# SCH_OnBoard_2023-10-19.net
KiCad netlist of a schematic drawn in EasyEDA
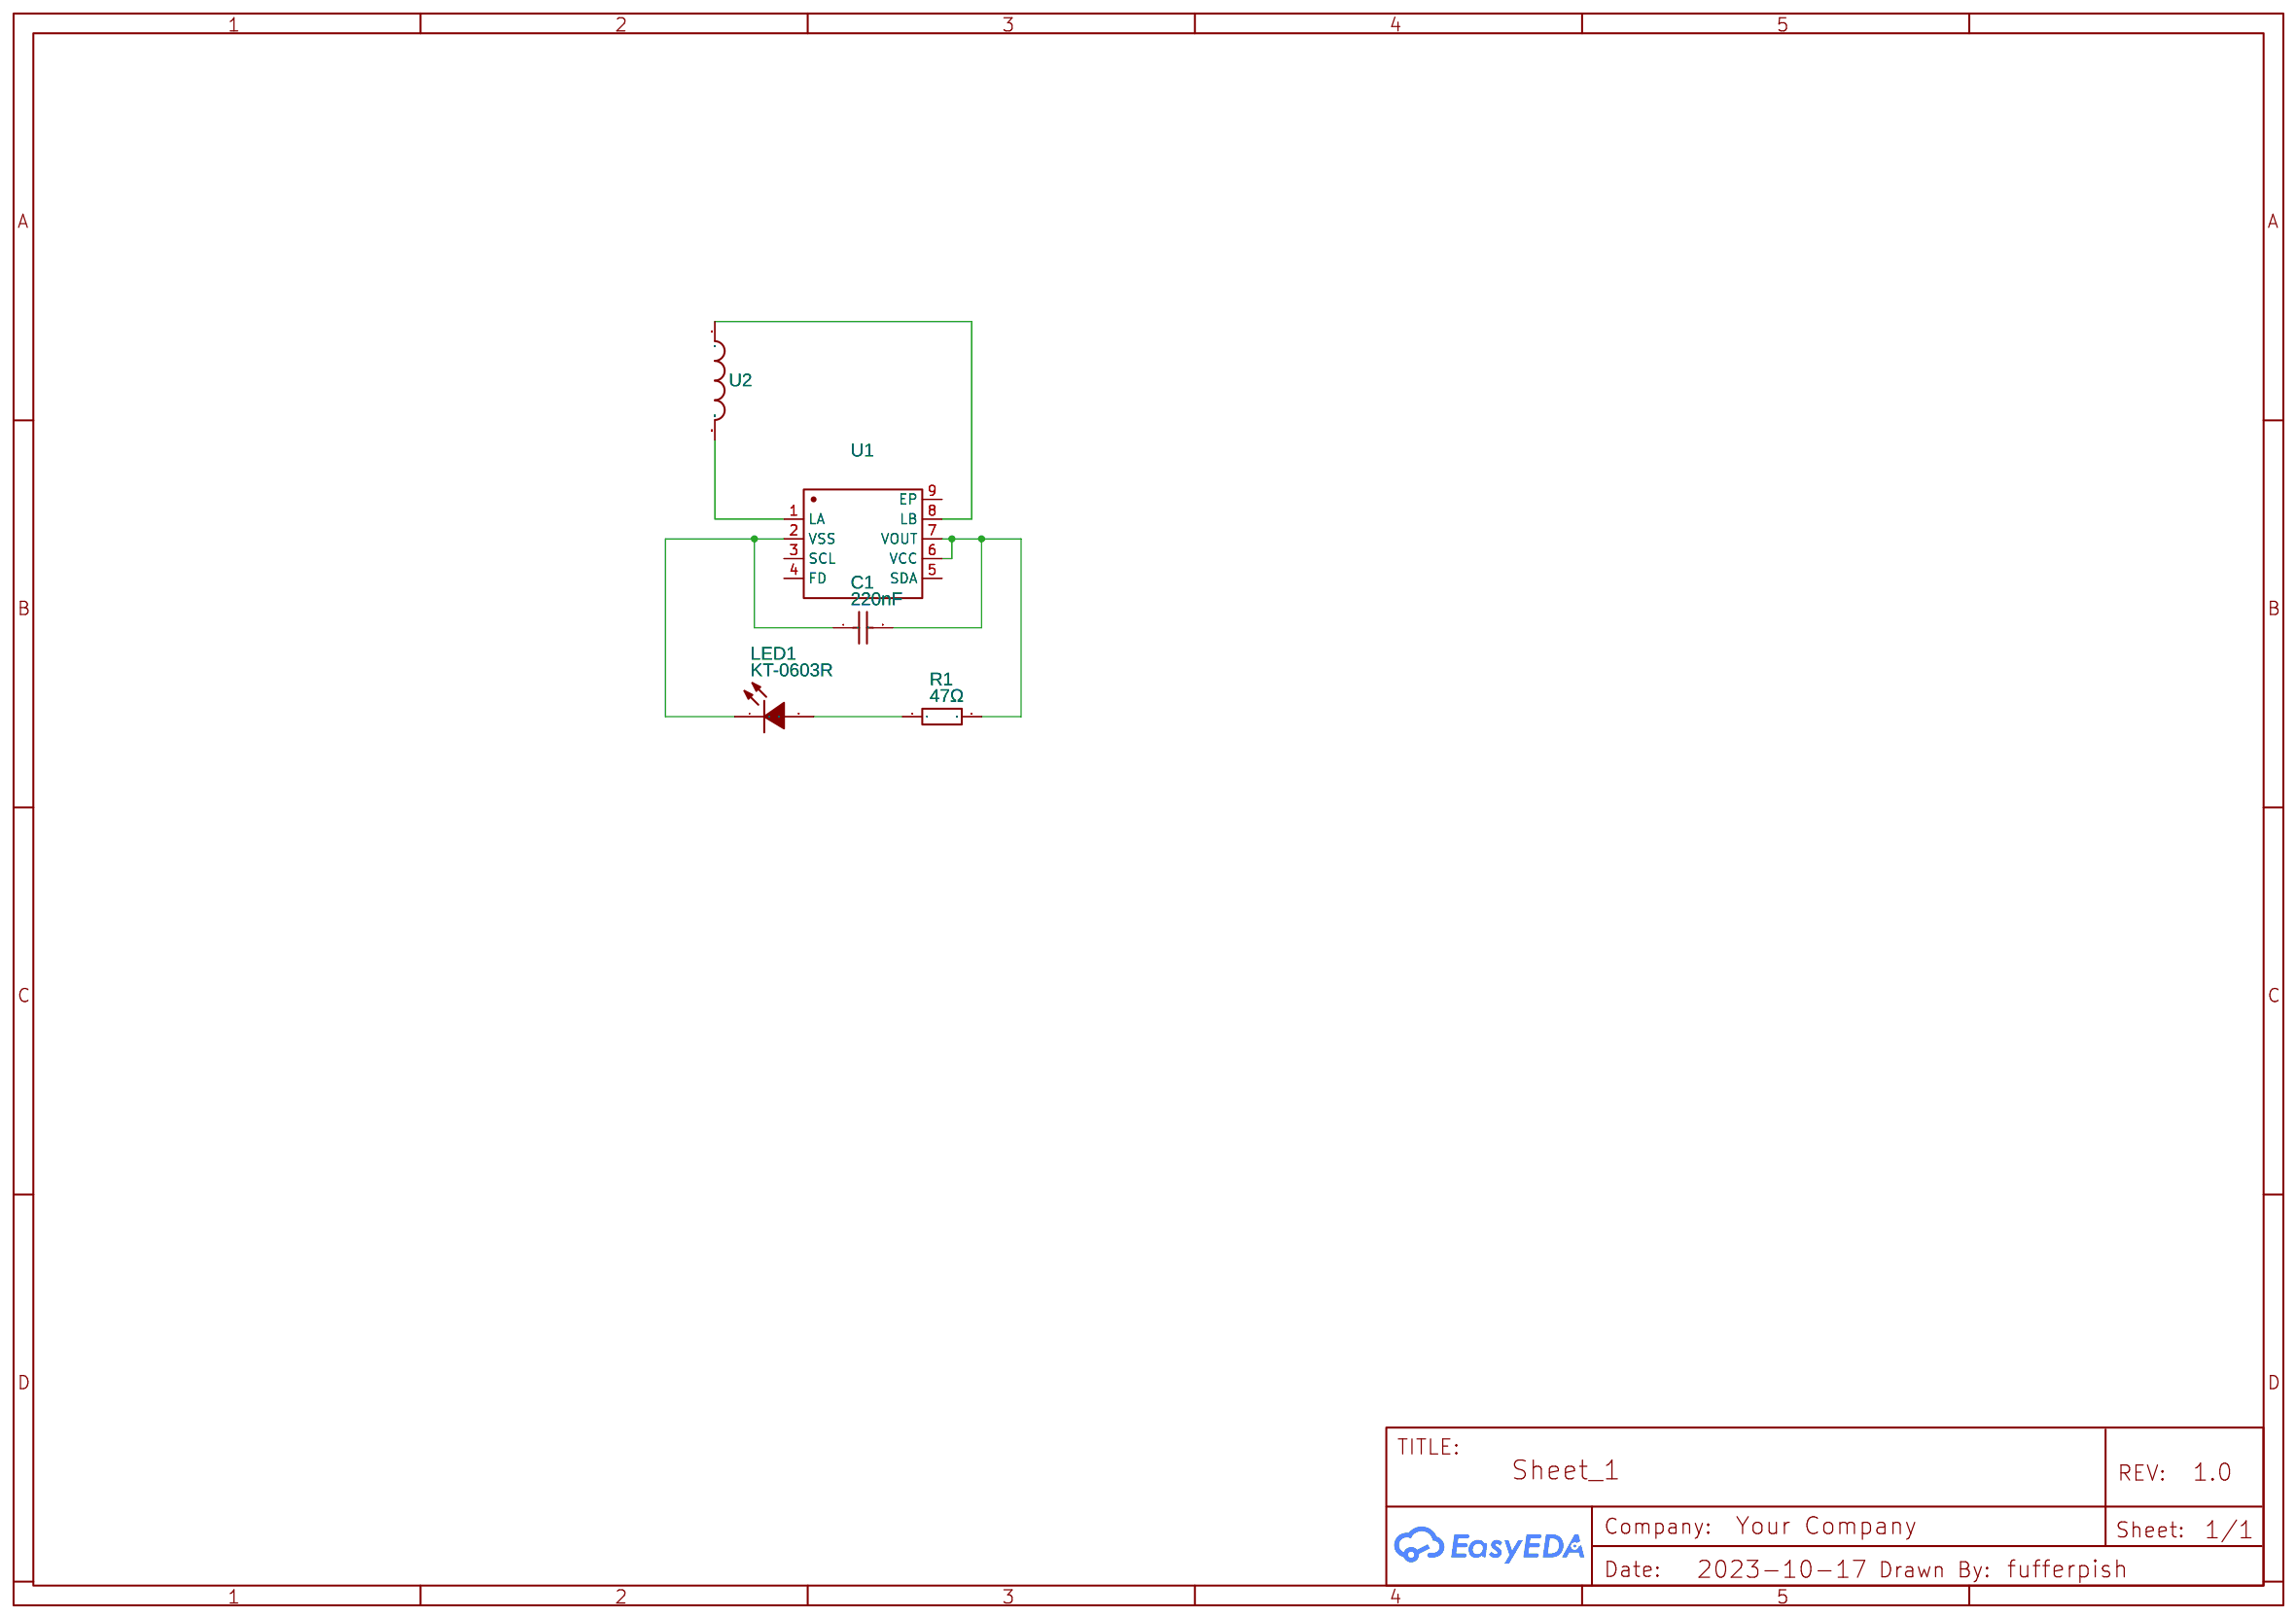
[diagram p0: schematic sheet]

(export (version "E")
  (design (tool "Eeschema 10.0.6"))
  (components
    (comp (ref "C1")
      (value "220nF")
      (fields
        (field (name "Manufacturer Part") "CL10B224KA8NNNC")
        (field (name "Manufacturer") "SAMSUNG(三星)")
      )
      (libsource (lib "") (part "CL10B224KA8NNNC"))
    )
    (comp (ref "LED1")
      (value "KT-0603R")
      (fields (field (name "Manufacturer") "KENTO"))
      (libsource (lib "") (part "KT-0603R"))
    )
    (comp (ref "R1")
      (value "47Ω")
      (fields
        (field (name "Manufacturer Part") "0603WAF470JT5E")
        (field (name "Manufacturer") "UNI-ROYAL(厚声)")
      )
      (libsource (lib "") (part "0603WAF470JT5E"))
    )
    (comp (ref "U1")
      (value "NT3H2111W0FHKH")
      (fields (field (name "Manufacturer") "NXP(恩智浦)"))
      (libsource (lib "") (part "NT3H2111W0FHKH"))
    )
    (comp (ref "U2") (value "NO") (libsource (lib "") (part "25X48MM_NFC_ANTENNA")))
  )
  (nets
    (net (code "1") (name "Net-(LED1-A)") (class "Default")
      (node (ref "LED1") (pin "2") (pinfunction "A_2") (pintype "unspecified"))
      (node (ref "R1") (pin "1") (pinfunction "1_1") (pintype "input"))
    )
    (net (code "2") (name "Net-(LED1-K)") (class "Default")
      (node (ref "C1") (pin "1") (pinfunction "1_1") (pintype "input"))
      (node (ref "LED1") (pin "1") (pinfunction "K_1") (pintype "unspecified"))
      (node (ref "U1") (pin "2") (pinfunction "VSS_2") (pintype "unspecified"))
    )
    (net (code "3") (name "Net-(U1-LA)") (class "Default")
      (node (ref "U1") (pin "1") (pinfunction "LA_1") (pintype "unspecified"))
      (node (ref "U2") (pin "P$2") (pinfunction "P$2_P$2") (pintype "bidirectional"))
    )
    (net (code "4") (name "Net-(U1-LB)") (class "Default")
      (node (ref "U1") (pin "8") (pinfunction "LB_8") (pintype "unspecified"))
      (node (ref "U2") (pin "P$1") (pinfunction "P$1_P$1") (pintype "bidirectional"))
    )
    (net (code "5") (name "Net-(U1-VCC)") (class "Default")
      (node (ref "C1") (pin "2") (pinfunction "2_2") (pintype "input"))
      (node (ref "R1") (pin "2") (pinfunction "2_2") (pintype "input"))
      (node (ref "U1") (pin "6") (pinfunction "VCC_6") (pintype "unspecified"))
      (node (ref "U1") (pin "7") (pinfunction "VOUT_7") (pintype "unspecified"))
    )
    (net (code "6") (name "unconnected-(U1-EP-Pad9)") (class "Default")
      (node (ref "U1") (pin "9") (pinfunction "EP_9") (pintype "unspecified"))
    )
    (net (code "7") (name "unconnected-(U1-FD-Pad4)") (class "Default")
      (node (ref "U1") (pin "4") (pinfunction "FD_4") (pintype "unspecified"))
    )
    (net (code "8") (name "unconnected-(U1-SCL-Pad3)") (class "Default")
      (node (ref "U1") (pin "3") (pinfunction "SCL_3") (pintype "unspecified"))
    )
    (net (code "9") (name "unconnected-(U1-SDA-Pad5)") (class "Default")
      (node (ref "U1") (pin "5") (pinfunction "SDA_5") (pintype "unspecified"))
    )
  )
)
